# breakout-lrtb-g6tg_light.net
KiCad netlist of a schematic drawn in EAGLE
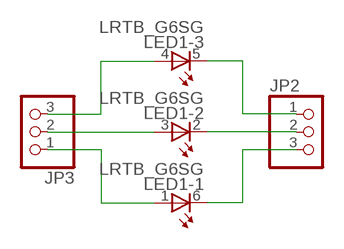
[diagram p0: schematic, sheet 1]

(export (version "E")
  (design (tool "Eeschema 10.0.6"))
  (components
    (comp (ref "JP2")
      (value "PINHD-1X3")
      (footprint "eagle-import:1X03")
      (libsource (lib "eagle-import") (part "PINHD-1X3"))
    )
    (comp (ref "JP3")
      (value "PINHD-1X3")
      (footprint "eagle-import:1X03")
      (libsource (lib "eagle-import") (part "PINHD-1X3"))
    )
    (comp (ref "LED1")
      (value "LRTB_G6SG")
      (footprint "eagle-import:LRTB_G6SG")
      (libsource (lib "eagle-import") (part "LRTB_G6SG"))
    )
  )
  (nets
    (net (code "1") (name "Net-(LED1A-A)") (class "Default")
      (node (ref "JP3") (pin "1") (pinfunction "1_1") (pintype "passive"))
      (node (ref "LED1") (pin "1") (pinfunction "A_1") (pintype "passive"))
    )
    (net (code "2") (name "Net-(LED1A-C)") (class "Default")
      (node (ref "JP2") (pin "3") (pinfunction "3_3") (pintype "passive"))
      (node (ref "LED1") (pin "6") (pinfunction "C_6") (pintype "passive"))
    )
    (net (code "3") (name "Net-(LED1B-A)") (class "Default")
      (node (ref "JP3") (pin "2") (pinfunction "2_2") (pintype "passive"))
      (node (ref "LED1") (pin "3") (pinfunction "A_3") (pintype "passive"))
    )
    (net (code "4") (name "Net-(LED1B-C)") (class "Default")
      (node (ref "JP2") (pin "2") (pinfunction "2_2") (pintype "passive"))
      (node (ref "LED1") (pin "2") (pinfunction "C_2") (pintype "passive"))
    )
    (net (code "5") (name "Net-(LED1C-A)") (class "Default")
      (node (ref "JP3") (pin "3") (pinfunction "3_3") (pintype "passive"))
      (node (ref "LED1") (pin "4") (pinfunction "A_4") (pintype "passive"))
    )
    (net (code "6") (name "Net-(LED1C-C)") (class "Default")
      (node (ref "JP2") (pin "1") (pinfunction "1_1") (pintype "passive"))
      (node (ref "LED1") (pin "5") (pinfunction "C_5") (pintype "passive"))
    )
  )
)
